# Control_Module_PER.net
KiCad netlist of a schematic drawn in Altium Designer
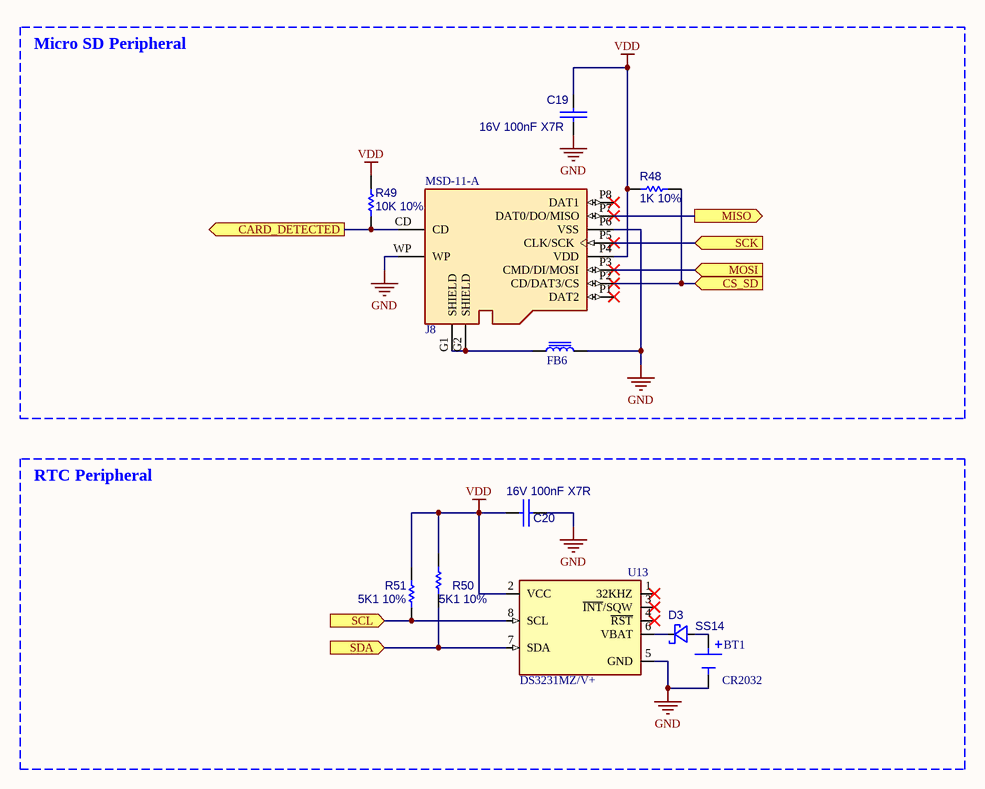
[diagram p0: Control_Module_PER.SchDoc]

(export (version "E")
  (design (tool "Eeschema 10.0.6"))
  (components
    (comp (ref "BT1")
      (value "CR2032")
      (footprint "KEYSTONE_1063TR_1063TR")
      (description "Battery Holder Coin 20 SMT Nickel T&R")
      (fields (field (name "MF") "TE Connectivity") (field (name "MP") "BAT-HLD-011-THM"))
      (libsource (lib "Control_Module_Symbols") (part "BAT-HLD-011-THM"))
    )
    (comp (ref "C19")
      (value "16V 100nF X7R")
      (footprint "CAP0402")
      (description "Non Polarized Capacitor")
      (libsource (lib "Control_Module_Symbols") (part "CAP"))
    )
    (comp (ref "C20")
      (value "16V 100nF X7R")
      (footprint "CAP0402")
      (description "Non Polarized Capacitor")
      (libsource (lib "Control_Module_Symbols") (part "CAP"))
    )
    (comp (ref "D3")
      (value "SS14")
      (footprint "D_SMA")
      (description "Diode Shottky")
      (libsource (lib "Control_Module_Symbols") (part "DIODO_SH"))
    )
    (comp (ref "FB6")
      (value "Choke 450mΩ ±25%")
      (footprint "CHOKE0603")
      (description "High Frequency EMI Suppression Ferrite Bead")
      (fields
        (field (name "MANUFACTURER PART NUMBER") "742863160")
        (field (name "MANUFACTURER") "Wurth Elektronik")
      )
      (libsource (lib "Control_Module_Symbols") (part "Choke"))
    )
    (comp (ref "J8")
      (value "MSD-11-A")
      (footprint "CUI_MSD-11-A")
      (fields (field (name "MF") "Same Sky"))
      (libsource (lib "Control_Module_Symbols") (part "MSD-11-A"))
    )
    (comp (ref "R48")
      (value "1K 10%")
      (footprint "RES0402")
      (description "Resistor")
      (libsource (lib "Control_Module_Symbols") (part "Res1"))
    )
    (comp (ref "R49")
      (value "10K 10%")
      (footprint "RES0402")
      (description "Resistor")
      (libsource (lib "Control_Module_Symbols") (part "Res1"))
    )
    (comp (ref "R50")
      (value "5K1 10%")
      (footprint "RES0402")
      (description "Resistor")
      (libsource (lib "Control_Module_Symbols") (part "Res1"))
    )
    (comp (ref "R51")
      (value "5K1 10%")
      (footprint "RES0402")
      (description "Resistor")
      (libsource (lib "Control_Module_Symbols") (part "Res1"))
    )
    (comp (ref "U13")
      (value "DS3231MZ/V+")
      (footprint "21-0041B_8")
      (description "±5ppm, I2C Real-Time Clock")
      (fields (field (name "MF") "Analog Devices"))
      (libsource (lib "Control_Module_Symbols") (part "DS3231MZ/V+"))
    )
  )
  (nets
    (net (code "1") (name "/CARD_DETECTED") (class "Default")
      (node (ref "J8") (pin "CD") (pinfunction "CD_CD") (pintype "passive"))
      (node (ref "R49") (pin "2") (pinfunction "2_2") (pintype "passive"))
    )
    (net (code "2") (name "/CS_SD") (class "Default")
      (node (ref "J8") (pin "P2") (pinfunction "CD/DAT3/CS_P2") (pintype "bidirectional"))
      (node (ref "R48") (pin "2") (pinfunction "2_2") (pintype "passive"))
    )
    (net (code "3") (name "/MISO") (class "Default")
      (node (ref "J8") (pin "P7") (pinfunction "DAT0/DO/MISO_P7") (pintype "bidirectional+no_connect"))
    )
    (net (code "4") (name "/MOSI") (class "Default")
      (node (ref "J8") (pin "P3") (pinfunction "CMD/DI/MOSI_P3") (pintype "bidirectional+no_connect"))
    )
    (net (code "5") (name "/SCK") (class "Default")
      (node (ref "J8") (pin "P5") (pinfunction "CLK/SCK_P5") (pintype "input+no_connect"))
    )
    (net (code "6") (name "/SCL") (class "Default")
      (node (ref "R51") (pin "2") (pinfunction "2_2") (pintype "passive"))
      (node (ref "U13") (pin "8") (pinfunction "SCL_8") (pintype "input"))
    )
    (net (code "7") (name "/SDA") (class "Default")
      (node (ref "R50") (pin "2") (pinfunction "2_2") (pintype "passive"))
      (node (ref "U13") (pin "7") (pinfunction "SDA_7") (pintype "input"))
    )
    (net (code "8") (name "GND") (class "Default")
      (node (ref "BT1") (pin "N") (pinfunction "N_N") (pintype "passive"))
      (node (ref "C19") (pin "2") (pinfunction "2_2") (pintype "passive"))
      (node (ref "C20") (pin "2") (pinfunction "2_2") (pintype "passive"))
      (node (ref "FB6") (pin "2") (pinfunction "2_2") (pintype "passive"))
      (node (ref "J8") (pin "P6") (pinfunction "VSS_P6") (pintype "power_in"))
      (node (ref "J8") (pin "WP") (pinfunction "WP_WP") (pintype "passive"))
      (node (ref "U13") (pin "5") (pinfunction "GND_5") (pintype "power_in"))
    )
    (net (code "9") (name "Net-(D3-A)") (class "Default")
      (node (ref "BT1") (pin "P") (pinfunction "P_P") (pintype "passive"))
      (node (ref "D3") (pin "1") (pinfunction "A_1") (pintype "passive"))
    )
    (net (code "10") (name "Net-(D3-K)") (class "Default")
      (node (ref "D3") (pin "2") (pinfunction "K_2") (pintype "passive"))
      (node (ref "U13") (pin "6") (pinfunction "VBAT_6") (pintype "power_in"))
    )
    (net (code "11") (name "Net-(FB6-Pad1)") (class "Default")
      (node (ref "FB6") (pin "1") (pinfunction "1_1") (pintype "passive"))
      (node (ref "J8") (pin "G1") (pinfunction "SHIELD_G1") (pintype "power_in"))
      (node (ref "J8") (pin "G2") (pinfunction "SHIELD_G2") (pintype "power_in"))
    )
    (net (code "12") (name "VDD") (class "Default")
      (node (ref "C19") (pin "1") (pinfunction "1_1") (pintype "passive"))
      (node (ref "C20") (pin "1") (pinfunction "1_1") (pintype "passive"))
      (node (ref "J8") (pin "P4") (pinfunction "VDD_P4") (pintype "power_in"))
      (node (ref "R48") (pin "1") (pinfunction "1_1") (pintype "passive"))
      (node (ref "R49") (pin "1") (pinfunction "1_1") (pintype "passive"))
      (node (ref "R50") (pin "1") (pinfunction "1_1") (pintype "passive"))
      (node (ref "R51") (pin "1") (pinfunction "1_1") (pintype "passive"))
      (node (ref "U13") (pin "2") (pinfunction "VCC_2") (pintype "power_in"))
    )
    (net (code "13") (name "unconnected-(J8-DAT1-PadP8)") (class "Default")
      (node (ref "J8") (pin "P8") (pinfunction "DAT1_P8") (pintype "bidirectional+no_connect"))
    )
    (net (code "14") (name "unconnected-(J8-DAT2-PadP1)") (class "Default")
      (node (ref "J8") (pin "P1") (pinfunction "DAT2_P1") (pintype "bidirectional+no_connect"))
    )
    (net (code "15") (name "unconnected-(U13-32KHZ-Pad1)") (class "Default")
      (node (ref "U13") (pin "1") (pinfunction "32KHZ_1") (pintype "passive+no_connect"))
    )
    (net (code "16") (name "unconnected-(U13-~{INT}{slash}SQW-Pad3)") (class "Default")
      (node (ref "U13") (pin "3") (pinfunction "~{INT}/SQW_3") (pintype "passive+no_connect"))
    )
    (net (code "17") (name "unconnected-(U13-~{RST}-Pad4)") (class "Default")
      (node (ref "U13") (pin "4") (pinfunction "~{RST}_4") (pintype "passive+no_connect"))
    )
  )
)
